# FPGA_IO_MCU.net
KiCad netlist of a schematic drawn in Altium Designer
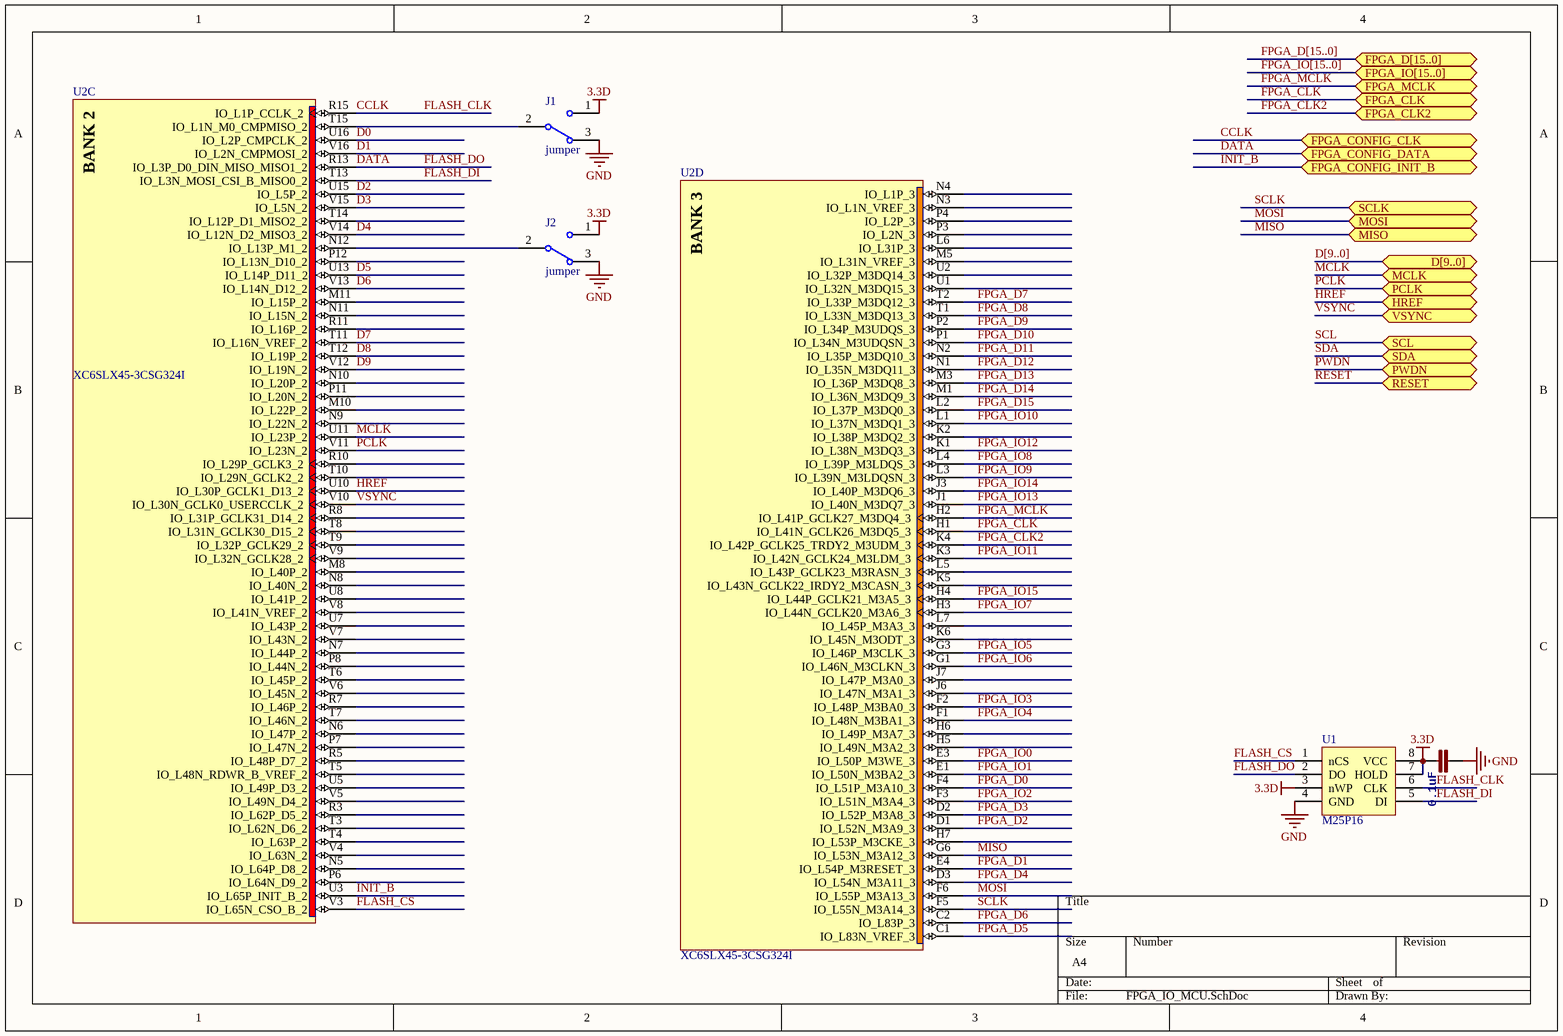
[diagram p0: FPGA_IO_MCU.SchDoc]

(export (version "E")
  (design (tool "Eeschema 10.0.6"))
  (components
    (comp (ref "C68")
      (value "0.1uF")
      (footprint "0402")
      (description "<b>Capacitor</b>\nStandard 0603 ceramic capacitor, and 0.1\" leaded capacitor.")
      (fields (field (name "PARTNO") "CC0402ZRY5V7BB104"))
      (libsource (lib "pixhawk2") (part "CAP0402-CAP"))
    )
    (comp (ref "J1")
      (value "jumper")
      (footprint "0402J")
      (description "SPDT Subminiature Toggle Switch, Right Angle Mounting, Vertical Actuation")
      (fields (field (name "PUBLISHER") "Altium Limited"))
      (libsource (lib "Miscellaneous Devices") (part "SW-SPDT"))
    )
    (comp (ref "J2")
      (value "jumper")
      (footprint "0402J")
      (description "SPDT Subminiature Toggle Switch, Right Angle Mounting, Vertical Actuation")
      (fields (field (name "PUBLISHER") "Altium Limited"))
      (libsource (lib "Miscellaneous Devices") (part "SW-SPDT"))
    )
    (comp (ref "U1") (value "M25P16") (footprint "SO8") (libsource (lib "sch") (part "M25P16")))
    (comp (ref "U2")
      (value "XC6SLX45-3CSG324I")
      (footprint "CSG324")
      (fields (field (name "PUBLISHER") "Altium Limited"))
      (libsource (lib "Xilinx Spartan-6") (part "XC6SLX45-3CSG324I"))
    )
  )
  (nets
    (net (code "1") (name "/CCLK") (class "Default")
      (node (ref "U1") (pin "6") (pinfunction "CLK_6") (pintype "passive"))
      (node (ref "U2") (pin "R15") (pinfunction "IO_L1P_CCLK_2_R15") (pintype "bidirectional"))
    )
    (net (code "2") (name "/D0") (class "Default")
      (node (ref "U2") (pin "U16") (pinfunction "IO_L2P_CMPCLK_2_U16") (pintype "bidirectional"))
    )
    (net (code "3") (name "/D1") (class "Default")
      (node (ref "U2") (pin "V16") (pinfunction "IO_L2N_CMPMOSI_2_V16") (pintype "bidirectional"))
    )
    (net (code "4") (name "/D2") (class "Default")
      (node (ref "U2") (pin "U15") (pinfunction "IO_L5P_2_U15") (pintype "bidirectional"))
    )
    (net (code "5") (name "/D3") (class "Default")
      (node (ref "U2") (pin "V15") (pinfunction "IO_L5N_2_V15") (pintype "bidirectional"))
    )
    (net (code "6") (name "/D4") (class "Default")
      (node (ref "U2") (pin "V14") (pinfunction "IO_L12N_D2_MISO3_2_V14") (pintype "bidirectional"))
    )
    (net (code "7") (name "/D5") (class "Default")
      (node (ref "U2") (pin "U13") (pinfunction "IO_L14P_D11_2_U13") (pintype "bidirectional"))
    )
    (net (code "8") (name "/D6") (class "Default")
      (node (ref "U2") (pin "V13") (pinfunction "IO_L14N_D12_2_V13") (pintype "bidirectional"))
    )
    (net (code "9") (name "/D7") (class "Default")
      (node (ref "U2") (pin "T11") (pinfunction "IO_L16N_VREF_2_T11") (pintype "bidirectional"))
    )
    (net (code "10") (name "/D8") (class "Default")
      (node (ref "U2") (pin "T12") (pinfunction "IO_L19P_2_T12") (pintype "bidirectional"))
    )
    (net (code "11") (name "/D9") (class "Default")
      (node (ref "U2") (pin "V12") (pinfunction "IO_L19N_2_V12") (pintype "bidirectional"))
    )
    (net (code "12") (name "/DATA") (class "Default")
      (node (ref "U1") (pin "2") (pinfunction "DO_2") (pintype "passive"))
      (node (ref "U2") (pin "R13") (pinfunction "IO_L3P_D0_DIN_MISO_MISO1_2_R13") (pintype "bidirectional"))
    )
    (net (code "14") (name "/FLASH_CS") (class "Default")
      (node (ref "U1") (pin "1") (pinfunction "nCS_1") (pintype "passive"))
      (node (ref "U2") (pin "V3") (pinfunction "IO_L65N_CSO_B_2_V3") (pintype "bidirectional"))
    )
    (net (code "15") (name "/FLASH_DI") (class "Default")
      (node (ref "U1") (pin "5") (pinfunction "DI_5") (pintype "passive"))
      (node (ref "U2") (pin "T13") (pinfunction "IO_L3N_MOSI_CSI_B_MISO0_2_T13") (pintype "bidirectional"))
    )
    (net (code "16") (name "/FPGA_CLK") (class "Default")
      (node (ref "U2") (pin "H1") (pinfunction "IO_L41N_GCLK26_M3DQ5_3_H1") (pintype "bidirectional"))
    )
    (net (code "17") (name "/FPGA_CLK2") (class "Default")
      (node (ref "U2") (pin "K4") (pinfunction "IO_L42P_GCLK25_TRDY2_M3UDM_3_K4") (pintype "bidirectional"))
    )
    (net (code "18") (name "/FPGA_D0") (class "Default")
      (node (ref "U2") (pin "F4") (pinfunction "IO_L51P_M3A10_3_F4") (pintype "bidirectional"))
    )
    (net (code "19") (name "/FPGA_D1") (class "Default")
      (node (ref "U2") (pin "E4") (pinfunction "IO_L54P_M3RESET_3_E4") (pintype "bidirectional"))
    )
    (net (code "20") (name "/FPGA_D2") (class "Default")
      (node (ref "U2") (pin "D1") (pinfunction "IO_L52N_M3A9_3_D1") (pintype "bidirectional"))
    )
    (net (code "21") (name "/FPGA_D3") (class "Default")
      (node (ref "U2") (pin "D2") (pinfunction "IO_L52P_M3A8_3_D2") (pintype "bidirectional"))
    )
    (net (code "22") (name "/FPGA_D4") (class "Default")
      (node (ref "U2") (pin "D3") (pinfunction "IO_L54N_M3A11_3_D3") (pintype "bidirectional"))
    )
    (net (code "23") (name "/FPGA_D5") (class "Default")
      (node (ref "U2") (pin "C1") (pinfunction "IO_L83N_VREF_3_C1") (pintype "bidirectional"))
    )
    (net (code "24") (name "/FPGA_D6") (class "Default")
      (node (ref "U2") (pin "C2") (pinfunction "IO_L83P_3_C2") (pintype "bidirectional"))
    )
    (net (code "25") (name "/FPGA_D7") (class "Default")
      (node (ref "U2") (pin "T2") (pinfunction "IO_L33P_M3DQ12_3_T2") (pintype "bidirectional"))
    )
    (net (code "26") (name "/FPGA_D8") (class "Default")
      (node (ref "U2") (pin "T1") (pinfunction "IO_L33N_M3DQ13_3_T1") (pintype "bidirectional"))
    )
    (net (code "27") (name "/FPGA_D9") (class "Default")
      (node (ref "U2") (pin "P2") (pinfunction "IO_L34P_M3UDQS_3_P2") (pintype "bidirectional"))
    )
    (net (code "28") (name "/FPGA_D10") (class "Default")
      (node (ref "U2") (pin "P1") (pinfunction "IO_L34N_M3UDQSN_3_P1") (pintype "bidirectional"))
    )
    (net (code "29") (name "/FPGA_D11") (class "Default")
      (node (ref "U2") (pin "N2") (pinfunction "IO_L35P_M3DQ10_3_N2") (pintype "bidirectional"))
    )
    (net (code "30") (name "/FPGA_D12") (class "Default")
      (node (ref "U2") (pin "N1") (pinfunction "IO_L35N_M3DQ11_3_N1") (pintype "bidirectional"))
    )
    (net (code "31") (name "/FPGA_D13") (class "Default")
      (node (ref "U2") (pin "M3") (pinfunction "IO_L36P_M3DQ8_3_M3") (pintype "bidirectional"))
    )
    (net (code "32") (name "/FPGA_D14") (class "Default")
      (node (ref "U2") (pin "M1") (pinfunction "IO_L36N_M3DQ9_3_M1") (pintype "bidirectional"))
    )
    (net (code "33") (name "/FPGA_D15") (class "Default")
      (node (ref "U2") (pin "L2") (pinfunction "IO_L37P_M3DQ0_3_L2") (pintype "bidirectional"))
    )
    (net (code "35") (name "/FPGA_IO0") (class "Default")
      (node (ref "U2") (pin "E3") (pinfunction "IO_L50P_M3WE_3_E3") (pintype "bidirectional"))
    )
    (net (code "36") (name "/FPGA_IO1") (class "Default")
      (node (ref "U2") (pin "E1") (pinfunction "IO_L50N_M3BA2_3_E1") (pintype "bidirectional"))
    )
    (net (code "37") (name "/FPGA_IO2") (class "Default")
      (node (ref "U2") (pin "F3") (pinfunction "IO_L51N_M3A4_3_F3") (pintype "bidirectional"))
    )
    (net (code "38") (name "/FPGA_IO3") (class "Default")
      (node (ref "U2") (pin "F2") (pinfunction "IO_L48P_M3BA0_3_F2") (pintype "bidirectional"))
    )
    (net (code "39") (name "/FPGA_IO4") (class "Default")
      (node (ref "U2") (pin "F1") (pinfunction "IO_L48N_M3BA1_3_F1") (pintype "bidirectional"))
    )
    (net (code "40") (name "/FPGA_IO5") (class "Default")
      (node (ref "U2") (pin "G3") (pinfunction "IO_L46P_M3CLK_3_G3") (pintype "bidirectional"))
    )
    (net (code "41") (name "/FPGA_IO6") (class "Default")
      (node (ref "U2") (pin "G1") (pinfunction "IO_L46N_M3CLKN_3_G1") (pintype "bidirectional"))
    )
    (net (code "42") (name "/FPGA_IO7") (class "Default")
      (node (ref "U2") (pin "H3") (pinfunction "IO_L44N_GCLK20_M3A6_3_H3") (pintype "bidirectional"))
    )
    (net (code "43") (name "/FPGA_IO8") (class "Default")
      (node (ref "U2") (pin "L4") (pinfunction "IO_L39P_M3LDQS_3_L4") (pintype "bidirectional"))
    )
    (net (code "44") (name "/FPGA_IO9") (class "Default")
      (node (ref "U2") (pin "L3") (pinfunction "IO_L39N_M3LDQSN_3_L3") (pintype "bidirectional"))
    )
    (net (code "45") (name "/FPGA_IO10") (class "Default")
      (node (ref "U2") (pin "L1") (pinfunction "IO_L37N_M3DQ1_3_L1") (pintype "bidirectional"))
    )
    (net (code "46") (name "/FPGA_IO11") (class "Default")
      (node (ref "U2") (pin "K3") (pinfunction "IO_L42N_GCLK24_M3LDM_3_K3") (pintype "bidirectional"))
    )
    (net (code "47") (name "/FPGA_IO12") (class "Default")
      (node (ref "U2") (pin "K1") (pinfunction "IO_L38N_M3DQ3_3_K1") (pintype "bidirectional"))
    )
    (net (code "48") (name "/FPGA_IO13") (class "Default")
      (node (ref "U2") (pin "J1") (pinfunction "IO_L40N_M3DQ7_3_J1") (pintype "bidirectional"))
    )
    (net (code "49") (name "/FPGA_IO14") (class "Default")
      (node (ref "U2") (pin "J3") (pinfunction "IO_L40P_M3DQ6_3_J3") (pintype "bidirectional"))
    )
    (net (code "50") (name "/FPGA_IO15") (class "Default")
      (node (ref "U2") (pin "H4") (pinfunction "IO_L44P_GCLK21_M3A5_3_H4") (pintype "bidirectional"))
    )
    (net (code "52") (name "/FPGA_MCLK") (class "Default")
      (node (ref "U2") (pin "H2") (pinfunction "IO_L41P_GCLK27_M3DQ4_3_H2") (pintype "bidirectional"))
    )
    (net (code "53") (name "/HREF") (class "Default")
      (node (ref "U2") (pin "U10") (pinfunction "IO_L30P_GCLK1_D13_2_U10") (pintype "bidirectional"))
    )
    (net (code "54") (name "/INIT_B") (class "Default")
      (node (ref "U2") (pin "U3") (pinfunction "IO_L65P_INIT_B_2_U3") (pintype "bidirectional"))
    )
    (net (code "55") (name "/MCLK") (class "Default")
      (node (ref "U2") (pin "U11") (pinfunction "IO_L23P_2_U11") (pintype "bidirectional"))
    )
    (net (code "56") (name "/MISO") (class "Default")
      (node (ref "U2") (pin "G6") (pinfunction "IO_L53N_M3A12_3_G6") (pintype "bidirectional"))
    )
    (net (code "57") (name "/MOSI") (class "Default")
      (node (ref "U2") (pin "F6") (pinfunction "IO_L55P_M3A13_3_F6") (pintype "bidirectional"))
    )
    (net (code "58") (name "/PCLK") (class "Default")
      (node (ref "U2") (pin "V11") (pinfunction "IO_L23N_2_V11") (pintype "bidirectional"))
    )
    (net (code "62") (name "/SCLK") (class "Default")
      (node (ref "U2") (pin "F5") (pinfunction "IO_L55N_M3A14_3_F5") (pintype "bidirectional"))
    )
    (net (code "64") (name "/VSYNC") (class "Default")
      (node (ref "U2") (pin "V10") (pinfunction "IO_L30N_GCLK0_USERCCLK_2_V10") (pintype "bidirectional"))
    )
    (net (code "65") (name "3.3D") (class "Default")
      (node (ref "C68") (pin "2") (pinfunction "2_2") (pintype "passive"))
      (node (ref "J1") (pin "1") (pinfunction "1_1") (pintype "passive"))
      (node (ref "J2") (pin "1") (pinfunction "1_1") (pintype "passive"))
      (node (ref "U1") (pin "3") (pinfunction "nWP_3") (pintype "passive"))
      (node (ref "U1") (pin "7") (pinfunction "HOLD_7") (pintype "passive"))
      (node (ref "U1") (pin "8") (pinfunction "VCC_8") (pintype "passive"))
    )
    (net (code "66") (name "GND") (class "Default")
      (node (ref "C68") (pin "1") (pinfunction "1_1") (pintype "passive"))
      (node (ref "J1") (pin "3") (pinfunction "3_3") (pintype "passive"))
      (node (ref "J2") (pin "3") (pinfunction "3_3") (pintype "passive"))
      (node (ref "U1") (pin "4") (pinfunction "GND_4") (pintype "passive"))
    )
    (net (code "67") (name "Net-(U2C-IO_L1N_M0_CMPMISO_2)") (class "Default")
      (node (ref "J1") (pin "2") (pinfunction "2_2") (pintype "passive"))
      (node (ref "U2") (pin "T15") (pinfunction "IO_L1N_M0_CMPMISO_2_T15") (pintype "bidirectional"))
    )
    (net (code "68") (name "Net-(U2C-IO_L13P_M1_2)") (class "Default")
      (node (ref "J2") (pin "2") (pinfunction "2_2") (pintype "passive"))
      (node (ref "U2") (pin "N12") (pinfunction "IO_L13P_M1_2_N12") (pintype "bidirectional"))
    )
    (net (code "69") (name "unconnected-(U2C-IO_L12P_D1_MISO2_2-PadT14)") (class "Default")
      (node (ref "U2") (pin "T14") (pinfunction "IO_L12P_D1_MISO2_2_T14") (pintype "bidirectional"))
    )
    (net (code "70") (name "unconnected-(U2C-IO_L13N_D10_2-PadP12)") (class "Default")
      (node (ref "U2") (pin "P12") (pinfunction "IO_L13N_D10_2_P12") (pintype "bidirectional"))
    )
    (net (code "71") (name "unconnected-(U2C-IO_L15N_2-PadN11)") (class "Default")
      (node (ref "U2") (pin "N11") (pinfunction "IO_L15N_2_N11") (pintype "bidirectional"))
    )
    (net (code "72") (name "unconnected-(U2C-IO_L15P_2-PadM11)") (class "Default")
      (node (ref "U2") (pin "M11") (pinfunction "IO_L15P_2_M11") (pintype "bidirectional"))
    )
    (net (code "73") (name "unconnected-(U2C-IO_L16P_2-PadR11)") (class "Default")
      (node (ref "U2") (pin "R11") (pinfunction "IO_L16P_2_R11") (pintype "bidirectional"))
    )
    (net (code "74") (name "unconnected-(U2C-IO_L20N_2-PadP11)") (class "Default")
      (node (ref "U2") (pin "P11") (pinfunction "IO_L20N_2_P11") (pintype "bidirectional"))
    )
    (net (code "75") (name "unconnected-(U2C-IO_L20P_2-PadN10)") (class "Default")
      (node (ref "U2") (pin "N10") (pinfunction "IO_L20P_2_N10") (pintype "bidirectional"))
    )
    (net (code "76") (name "unconnected-(U2C-IO_L22N_2-PadN9)") (class "Default")
      (node (ref "U2") (pin "N9") (pinfunction "IO_L22N_2_N9") (pintype "bidirectional"))
    )
    (net (code "77") (name "unconnected-(U2C-IO_L22P_2-PadM10)") (class "Default")
      (node (ref "U2") (pin "M10") (pinfunction "IO_L22P_2_M10") (pintype "bidirectional"))
    )
    (net (code "78") (name "unconnected-(U2C-IO_L29N_GCLK2_2-PadT10)") (class "Default")
      (node (ref "U2") (pin "T10") (pinfunction "IO_L29N_GCLK2_2_T10") (pintype "bidirectional"))
    )
    (net (code "79") (name "unconnected-(U2C-IO_L29P_GCLK3_2-PadR10)") (class "Default")
      (node (ref "U2") (pin "R10") (pinfunction "IO_L29P_GCLK3_2_R10") (pintype "bidirectional"))
    )
    (net (code "80") (name "unconnected-(U2C-IO_L31N_GCLK30_D15_2-PadT8)") (class "Default")
      (node (ref "U2") (pin "T8") (pinfunction "IO_L31N_GCLK30_D15_2_T8") (pintype "bidirectional"))
    )
    (net (code "81") (name "unconnected-(U2C-IO_L31P_GCLK31_D14_2-PadR8)") (class "Default")
      (node (ref "U2") (pin "R8") (pinfunction "IO_L31P_GCLK31_D14_2_R8") (pintype "bidirectional"))
    )
    (net (code "82") (name "unconnected-(U2C-IO_L32N_GCLK28_2-PadV9)") (class "Default")
      (node (ref "U2") (pin "V9") (pinfunction "IO_L32N_GCLK28_2_V9") (pintype "bidirectional"))
    )
    (net (code "83") (name "unconnected-(U2C-IO_L32P_GCLK29_2-PadT9)") (class "Default")
      (node (ref "U2") (pin "T9") (pinfunction "IO_L32P_GCLK29_2_T9") (pintype "bidirectional"))
    )
    (net (code "84") (name "unconnected-(U2C-IO_L40N_2-PadN8)") (class "Default")
      (node (ref "U2") (pin "N8") (pinfunction "IO_L40N_2_N8") (pintype "bidirectional"))
    )
    (net (code "85") (name "unconnected-(U2C-IO_L40P_2-PadM8)") (class "Default")
      (node (ref "U2") (pin "M8") (pinfunction "IO_L40P_2_M8") (pintype "bidirectional"))
    )
    (net (code "86") (name "unconnected-(U2C-IO_L41N_VREF_2-PadV8)") (class "Default")
      (node (ref "U2") (pin "V8") (pinfunction "IO_L41N_VREF_2_V8") (pintype "bidirectional"))
    )
    (net (code "87") (name "unconnected-(U2C-IO_L41P_2-PadU8)") (class "Default")
      (node (ref "U2") (pin "U8") (pinfunction "IO_L41P_2_U8") (pintype "bidirectional"))
    )
    (net (code "88") (name "unconnected-(U2C-IO_L43N_2-PadV7)") (class "Default")
      (node (ref "U2") (pin "V7") (pinfunction "IO_L43N_2_V7") (pintype "bidirectional"))
    )
    (net (code "89") (name "unconnected-(U2C-IO_L43P_2-PadU7)") (class "Default")
      (node (ref "U2") (pin "U7") (pinfunction "IO_L43P_2_U7") (pintype "bidirectional"))
    )
    (net (code "90") (name "unconnected-(U2C-IO_L44N_2-PadP8)") (class "Default")
      (node (ref "U2") (pin "P8") (pinfunction "IO_L44N_2_P8") (pintype "bidirectional"))
    )
    (net (code "91") (name "unconnected-(U2C-IO_L44P_2-PadN7)") (class "Default")
      (node (ref "U2") (pin "N7") (pinfunction "IO_L44P_2_N7") (pintype "bidirectional"))
    )
    (net (code "92") (name "unconnected-(U2C-IO_L45N_2-PadV6)") (class "Default")
      (node (ref "U2") (pin "V6") (pinfunction "IO_L45N_2_V6") (pintype "bidirectional"))
    )
    (net (code "93") (name "unconnected-(U2C-IO_L45P_2-PadT6)") (class "Default")
      (node (ref "U2") (pin "T6") (pinfunction "IO_L45P_2_T6") (pintype "bidirectional"))
    )
    (net (code "94") (name "unconnected-(U2C-IO_L46N_2-PadT7)") (class "Default")
      (node (ref "U2") (pin "T7") (pinfunction "IO_L46N_2_T7") (pintype "bidirectional"))
    )
    (net (code "95") (name "unconnected-(U2C-IO_L46P_2-PadR7)") (class "Default")
      (node (ref "U2") (pin "R7") (pinfunction "IO_L46P_2_R7") (pintype "bidirectional"))
    )
    (net (code "96") (name "unconnected-(U2C-IO_L47N_2-PadP7)") (class "Default")
      (node (ref "U2") (pin "P7") (pinfunction "IO_L47N_2_P7") (pintype "bidirectional"))
    )
    (net (code "97") (name "unconnected-(U2C-IO_L47P_2-PadN6)") (class "Default")
      (node (ref "U2") (pin "N6") (pinfunction "IO_L47P_2_N6") (pintype "bidirectional"))
    )
    (net (code "98") (name "unconnected-(U2C-IO_L48N_RDWR_B_VREF_2-PadT5)") (class "Default")
      (node (ref "U2") (pin "T5") (pinfunction "IO_L48N_RDWR_B_VREF_2_T5") (pintype "bidirectional"))
    )
    (net (code "99") (name "unconnected-(U2C-IO_L48P_D7_2-PadR5)") (class "Default")
      (node (ref "U2") (pin "R5") (pinfunction "IO_L48P_D7_2_R5") (pintype "bidirectional"))
    )
    (net (code "100") (name "unconnected-(U2C-IO_L49N_D4_2-PadV5)") (class "Default")
      (node (ref "U2") (pin "V5") (pinfunction "IO_L49N_D4_2_V5") (pintype "bidirectional"))
    )
    (net (code "101") (name "unconnected-(U2C-IO_L49P_D3_2-PadU5)") (class "Default")
      (node (ref "U2") (pin "U5") (pinfunction "IO_L49P_D3_2_U5") (pintype "bidirectional"))
    )
    (net (code "102") (name "unconnected-(U2C-IO_L62N_D6_2-PadT3)") (class "Default")
      (node (ref "U2") (pin "T3") (pinfunction "IO_L62N_D6_2_T3") (pintype "bidirectional"))
    )
    (net (code "103") (name "unconnected-(U2C-IO_L62P_D5_2-PadR3)") (class "Default")
      (node (ref "U2") (pin "R3") (pinfunction "IO_L62P_D5_2_R3") (pintype "bidirectional"))
    )
    (net (code "104") (name "unconnected-(U2C-IO_L63N_2-PadV4)") (class "Default")
      (node (ref "U2") (pin "V4") (pinfunction "IO_L63N_2_V4") (pintype "bidirectional"))
    )
    (net (code "105") (name "unconnected-(U2C-IO_L63P_2-PadT4)") (class "Default")
      (node (ref "U2") (pin "T4") (pinfunction "IO_L63P_2_T4") (pintype "bidirectional"))
    )
    (net (code "106") (name "unconnected-(U2C-IO_L64N_D9_2-PadP6)") (class "Default")
      (node (ref "U2") (pin "P6") (pinfunction "IO_L64N_D9_2_P6") (pintype "bidirectional"))
    )
    (net (code "107") (name "unconnected-(U2C-IO_L64P_D8_2-PadN5)") (class "Default")
      (node (ref "U2") (pin "N5") (pinfunction "IO_L64P_D8_2_N5") (pintype "bidirectional"))
    )
    (net (code "108") (name "unconnected-(U2D-IO_L1N_VREF_3-PadN3)") (class "Default")
      (node (ref "U2") (pin "N3") (pinfunction "IO_L1N_VREF_3_N3") (pintype "bidirectional"))
    )
    (net (code "109") (name "unconnected-(U2D-IO_L1P_3-PadN4)") (class "Default")
      (node (ref "U2") (pin "N4") (pinfunction "IO_L1P_3_N4") (pintype "bidirectional"))
    )
    (net (code "110") (name "unconnected-(U2D-IO_L2N_3-PadP3)") (class "Default")
      (node (ref "U2") (pin "P3") (pinfunction "IO_L2N_3_P3") (pintype "bidirectional"))
    )
    (net (code "111") (name "unconnected-(U2D-IO_L2P_3-PadP4)") (class "Default")
      (node (ref "U2") (pin "P4") (pinfunction "IO_L2P_3_P4") (pintype "bidirectional"))
    )
    (net (code "112") (name "unconnected-(U2D-IO_L31N_VREF_3-PadM5)") (class "Default")
      (node (ref "U2") (pin "M5") (pinfunction "IO_L31N_VREF_3_M5") (pintype "bidirectional"))
    )
    (net (code "113") (name "unconnected-(U2D-IO_L31P_3-PadL6)") (class "Default")
      (node (ref "U2") (pin "L6") (pinfunction "IO_L31P_3_L6") (pintype "bidirectional"))
    )
    (net (code "114") (name "unconnected-(U2D-IO_L32N_M3DQ15_3-PadU1)") (class "Default")
      (node (ref "U2") (pin "U1") (pinfunction "IO_L32N_M3DQ15_3_U1") (pintype "bidirectional"))
    )
    (net (code "115") (name "unconnected-(U2D-IO_L32P_M3DQ14_3-PadU2)") (class "Default")
      (node (ref "U2") (pin "U2") (pinfunction "IO_L32P_M3DQ14_3_U2") (pintype "bidirectional"))
    )
    (net (code "116") (name "unconnected-(U2D-IO_L38P_M3DQ2_3-PadK2)") (class "Default")
      (node (ref "U2") (pin "K2") (pinfunction "IO_L38P_M3DQ2_3_K2") (pintype "bidirectional"))
    )
    (net (code "117") (name "unconnected-(U2D-IO_L43N_GCLK22_IRDY2_M3CASN_3-PadK5)") (class "Default")
      (node (ref "U2") (pin "K5") (pinfunction "IO_L43N_GCLK22_IRDY2_M3CASN_3_K5") (pintype "bidirectional"))
    )
    (net (code "118") (name "unconnected-(U2D-IO_L43P_GCLK23_M3RASN_3-PadL5)") (class "Default")
      (node (ref "U2") (pin "L5") (pinfunction "IO_L43P_GCLK23_M3RASN_3_L5") (pintype "bidirectional"))
    )
    (net (code "119") (name "unconnected-(U2D-IO_L45N_M3ODT_3-PadK6)") (class "Default")
      (node (ref "U2") (pin "K6") (pinfunction "IO_L45N_M3ODT_3_K6") (pintype "bidirectional"))
    )
    (net (code "120") (name "unconnected-(U2D-IO_L45P_M3A3_3-PadL7)") (class "Default")
      (node (ref "U2") (pin "L7") (pinfunction "IO_L45P_M3A3_3_L7") (pintype "bidirectional"))
    )
    (net (code "121") (name "unconnected-(U2D-IO_L47N_M3A1_3-PadJ6)") (class "Default")
      (node (ref "U2") (pin "J6") (pinfunction "IO_L47N_M3A1_3_J6") (pintype "bidirectional"))
    )
    (net (code "122") (name "unconnected-(U2D-IO_L47P_M3A0_3-PadJ7)") (class "Default")
      (node (ref "U2") (pin "J7") (pinfunction "IO_L47P_M3A0_3_J7") (pintype "bidirectional"))
    )
    (net (code "123") (name "unconnected-(U2D-IO_L49N_M3A2_3-PadH5)") (class "Default")
      (node (ref "U2") (pin "H5") (pinfunction "IO_L49N_M3A2_3_H5") (pintype "bidirectional"))
    )
    (net (code "124") (name "unconnected-(U2D-IO_L49P_M3A7_3-PadH6)") (class "Default")
      (node (ref "U2") (pin "H6") (pinfunction "IO_L49P_M3A7_3_H6") (pintype "bidirectional"))
    )
    (net (code "125") (name "unconnected-(U2D-IO_L53P_M3CKE_3-PadH7)") (class "Default")
      (node (ref "U2") (pin "H7") (pinfunction "IO_L53P_M3CKE_3_H7") (pintype "bidirectional"))
    )
  )
)
